# right_revision1_1.net
KiCad netlist of a schematic drawn in EAGLE
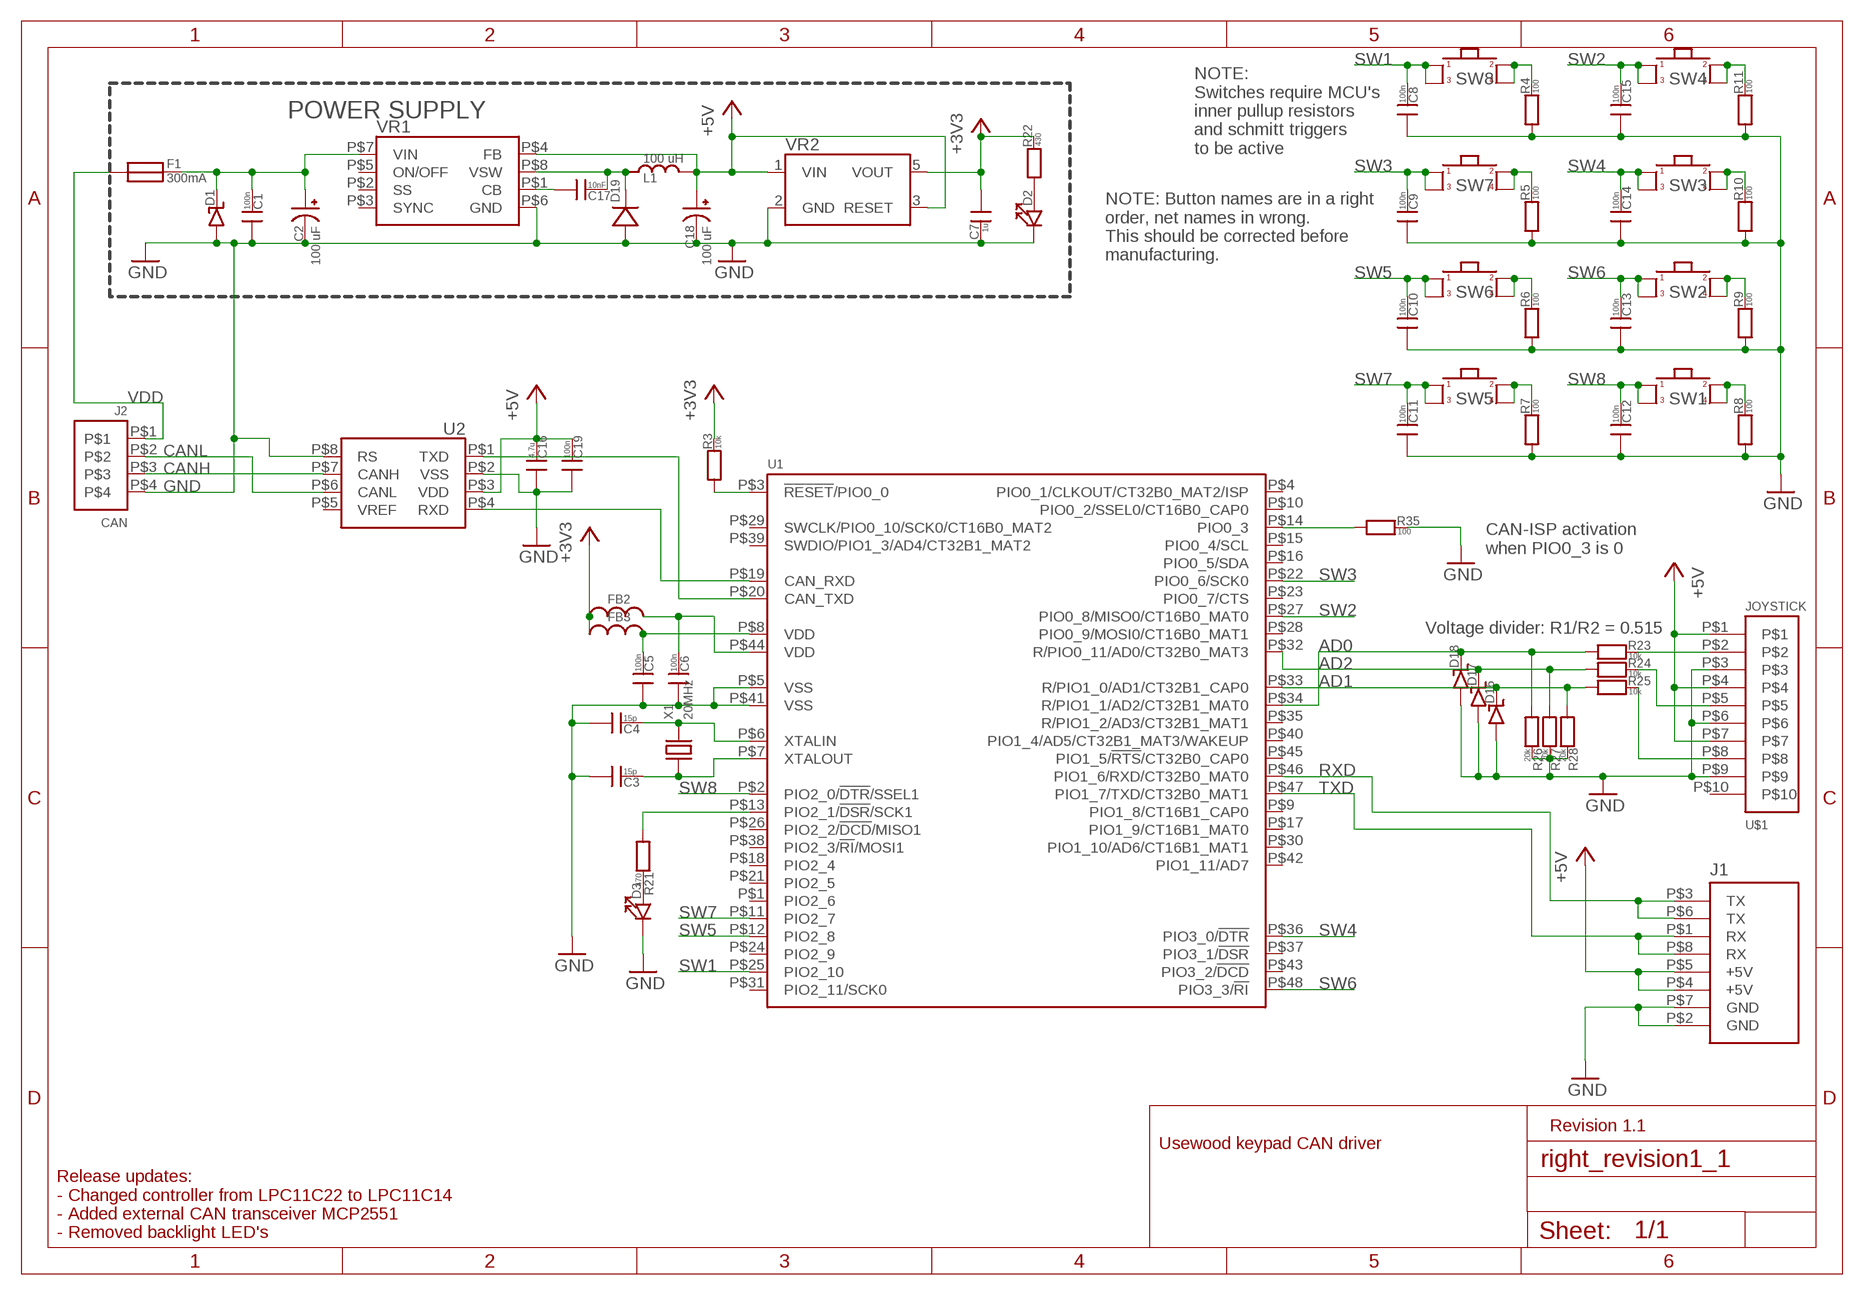
[diagram p0: schematic, sheet 1]

(export (version "E")
  (design (tool "Eeschema 10.0.6"))
  (components
    (comp (ref "C1")
      (value "100n")
      (footprint "eagle-import:0603_SILKSCREEN")
      (libsource (lib "eagle-import") (part "CAP0603_SILKSCREEN"))
    )
    (comp (ref "C2")
      (value "100 uF")
      (footprint "eagle-import:CAP_POL_SMD_10X10X10MM")
      (libsource (lib "eagle-import") (part "CAP_POLSMD_10X10X10MM"))
    )
    (comp (ref "C3")
      (value "15p")
      (footprint "eagle-import:0603_SILKSCREEN")
      (libsource (lib "eagle-import") (part "CAP0603_SILKSCREEN"))
    )
    (comp (ref "C4")
      (value "15p")
      (footprint "eagle-import:0603_SILKSCREEN")
      (libsource (lib "eagle-import") (part "CAP0603_SILKSCREEN"))
    )
    (comp (ref "C5")
      (value "100n")
      (footprint "eagle-import:0603_SILKSCREEN")
      (libsource (lib "eagle-import") (part "CAP0603_SILKSCREEN"))
    )
    (comp (ref "C6")
      (value "100n")
      (footprint "eagle-import:0603_SILKSCREEN")
      (libsource (lib "eagle-import") (part "CAP0603_SILKSCREEN"))
    )
    (comp (ref "C7")
      (value "1u")
      (footprint "eagle-import:0603_SILKSCREEN")
      (libsource (lib "eagle-import") (part "CAP0603_SILKSCREEN"))
    )
    (comp (ref "C8")
      (value "100n")
      (footprint "eagle-import:0603_SILKSCREEN")
      (libsource (lib "eagle-import") (part "CAP0603_SILKSCREEN"))
    )
    (comp (ref "C9")
      (value "100n")
      (footprint "eagle-import:0603_SILKSCREEN")
      (libsource (lib "eagle-import") (part "CAP0603_SILKSCREEN"))
    )
    (comp (ref "C10")
      (value "100n")
      (footprint "eagle-import:0603_SILKSCREEN")
      (libsource (lib "eagle-import") (part "CAP0603_SILKSCREEN"))
    )
    (comp (ref "C11")
      (value "100n")
      (footprint "eagle-import:0603_SILKSCREEN")
      (libsource (lib "eagle-import") (part "CAP0603_SILKSCREEN"))
    )
    (comp (ref "C12")
      (value "100n")
      (footprint "eagle-import:0603_SILKSCREEN")
      (libsource (lib "eagle-import") (part "CAP0603_SILKSCREEN"))
    )
    (comp (ref "C13")
      (value "100n")
      (footprint "eagle-import:0603_SILKSCREEN")
      (libsource (lib "eagle-import") (part "CAP0603_SILKSCREEN"))
    )
    (comp (ref "C14")
      (value "100n")
      (footprint "eagle-import:0603_SILKSCREEN")
      (libsource (lib "eagle-import") (part "CAP0603_SILKSCREEN"))
    )
    (comp (ref "C15")
      (value "100n")
      (footprint "eagle-import:0603_SILKSCREEN")
      (libsource (lib "eagle-import") (part "CAP0603_SILKSCREEN"))
    )
    (comp (ref "C16")
      (value "4.7u")
      (footprint "eagle-import:0603_SILKSCREEN")
      (libsource (lib "eagle-import") (part "CAP0603_SILKSCREEN"))
    )
    (comp (ref "C17")
      (value "10nF")
      (footprint "eagle-import:0603_SILKSCREEN")
      (libsource (lib "eagle-import") (part "CAP0603_SILKSCREEN"))
    )
    (comp (ref "C18")
      (value "100 uF")
      (footprint "eagle-import:CAP_POL_SMD_10X10X10MM")
      (libsource (lib "eagle-import") (part "CAP_POLSMD_10X10X10MM"))
    )
    (comp (ref "C19")
      (value "100n")
      (footprint "eagle-import:0603_SILKSCREEN")
      (libsource (lib "eagle-import") (part "CAP0603_SILKSCREEN"))
    )
    (comp (ref "D1")
      (value "DIODE_TVSDO-214AA")
      (footprint "eagle-import:DO-214AB")
      (libsource (lib "eagle-import") (part "DIODE_TVSDO-214AA"))
    )
    (comp (ref "D2")
      (value "LED0603_SILKSCREEN")
      (footprint "eagle-import:0603_SILKSCREEN")
      (libsource (lib "eagle-import") (part "LED0603_SILKSCREEN"))
    )
    (comp (ref "D3")
      (value "LED0603_SILKSCREEN")
      (footprint "eagle-import:0603_SILKSCREEN")
      (libsource (lib "eagle-import") (part "LED0603_SILKSCREEN"))
    )
    (comp (ref "D16")
      (value "DIODE_ZENERSDO123")
      (footprint "eagle-import:SOD123")
      (libsource (lib "eagle-import") (part "DIODE_ZENERSDO123"))
    )
    (comp (ref "D17")
      (value "DIODE_ZENERSDO123")
      (footprint "eagle-import:SOD123")
      (libsource (lib "eagle-import") (part "DIODE_ZENERSDO123"))
    )
    (comp (ref "D18")
      (value "DIODE_ZENERSDO123")
      (footprint "eagle-import:SOD123")
      (libsource (lib "eagle-import") (part "DIODE_ZENERSDO123"))
    )
    (comp (ref "D19")
      (value "DIODEDO219AB")
      (footprint "eagle-import:DO219AB")
      (libsource (lib "eagle-import") (part "DIODEDO219AB"))
    )
    (comp (ref "F1")
      (value "300mA")
      (footprint "eagle-import:FUSE_100MA")
      (libsource (lib "eagle-import") (part "FUSE100MA"))
    )
    (comp (ref "FB2")
      (value "FERRITE0603_SILKSCREEN")
      (footprint "eagle-import:0603_SILKSCREEN")
      (libsource (lib "eagle-import") (part "FERRITE0603_SILKSCREEN"))
    )
    (comp (ref "FB3")
      (value "FERRITE0603_SILKSCREEN")
      (footprint "eagle-import:0603_SILKSCREEN")
      (libsource (lib "eagle-import") (part "FERRITE0603_SILKSCREEN"))
    )
    (comp (ref "J1")
      (value "HEADER_USART_2_TH")
      (footprint "eagle-import:HEADER_USART_2_TH")
      (libsource (lib "eagle-import") (part "HEADER_USART_2_TH"))
    )
    (comp (ref "J2")
      (value "CAN")
      (footprint "eagle-import:MOLEX_MICRO-FIT_4WAY")
      (libsource (lib "eagle-import") (part "MOLEX_MICRO-FIT_4WAYTH"))
    )
    (comp (ref "L1")
      (value "100 uH")
      (footprint "eagle-import:INDUCTOR_BOURNS_10X13X5MM")
      (libsource (lib "eagle-import") (part "INDUCTORBOURNS_10X13X5MM"))
    )
    (comp (ref "R3")
      (value "10k")
      (footprint "eagle-import:0603_SILKSCREEN")
      (libsource (lib "eagle-import") (part "RES0604_SILKSCREEN"))
    )
    (comp (ref "R4")
      (value "100")
      (footprint "eagle-import:0603_SILKSCREEN")
      (libsource (lib "eagle-import") (part "RES0604_SILKSCREEN"))
    )
    (comp (ref "R5")
      (value "100")
      (footprint "eagle-import:0603_SILKSCREEN")
      (libsource (lib "eagle-import") (part "RES0604_SILKSCREEN"))
    )
    (comp (ref "R6")
      (value "100")
      (footprint "eagle-import:0603_SILKSCREEN")
      (libsource (lib "eagle-import") (part "RES0604_SILKSCREEN"))
    )
    (comp (ref "R7")
      (value "100")
      (footprint "eagle-import:0603_SILKSCREEN")
      (libsource (lib "eagle-import") (part "RES0604_SILKSCREEN"))
    )
    (comp (ref "R8")
      (value "100")
      (footprint "eagle-import:0603_SILKSCREEN")
      (libsource (lib "eagle-import") (part "RES0604_SILKSCREEN"))
    )
    (comp (ref "R9")
      (value "100")
      (footprint "eagle-import:0603_SILKSCREEN")
      (libsource (lib "eagle-import") (part "RES0604_SILKSCREEN"))
    )
    (comp (ref "R10")
      (value "100")
      (footprint "eagle-import:0603_SILKSCREEN")
      (libsource (lib "eagle-import") (part "RES0604_SILKSCREEN"))
    )
    (comp (ref "R11")
      (value "100")
      (footprint "eagle-import:0603_SILKSCREEN")
      (libsource (lib "eagle-import") (part "RES0604_SILKSCREEN"))
    )
    (comp (ref "R21")
      (value "470")
      (footprint "eagle-import:0603_SILKSCREEN")
      (libsource (lib "eagle-import") (part "RES0604_SILKSCREEN"))
    )
    (comp (ref "R22")
      (value "430")
      (footprint "eagle-import:0603_SILKSCREEN")
      (libsource (lib "eagle-import") (part "RES0604_SILKSCREEN"))
    )
    (comp (ref "R23")
      (value "10k")
      (footprint "eagle-import:0603_SILKSCREEN")
      (libsource (lib "eagle-import") (part "RES0604_SILKSCREEN"))
    )
    (comp (ref "R24")
      (value "10k")
      (footprint "eagle-import:0603_SILKSCREEN")
      (libsource (lib "eagle-import") (part "RES0604_SILKSCREEN"))
    )
    (comp (ref "R25")
      (value "10k")
      (footprint "eagle-import:0603_SILKSCREEN")
      (libsource (lib "eagle-import") (part "RES0604_SILKSCREEN"))
    )
    (comp (ref "R26")
      (value "20k")
      (footprint "eagle-import:0603_SILKSCREEN")
      (libsource (lib "eagle-import") (part "RES0604_SILKSCREEN"))
    )
    (comp (ref "R27")
      (value "20k")
      (footprint "eagle-import:0603_SILKSCREEN")
      (libsource (lib "eagle-import") (part "RES0604_SILKSCREEN"))
    )
    (comp (ref "R28")
      (value "20k")
      (footprint "eagle-import:0603_SILKSCREEN")
      (libsource (lib "eagle-import") (part "RES0604_SILKSCREEN"))
    )
    (comp (ref "R35")
      (value "100")
      (footprint "eagle-import:0603_SILKSCREEN")
      (libsource (lib "eagle-import") (part "RES0604_SILKSCREEN"))
    )
    (comp (ref "SW1")
      (value "SWITCH12X12MM_CENTER_HOLE")
      (footprint "eagle-import:SWITCH_12X12MM_CENTER_HOLE")
      (libsource (lib "eagle-import") (part "SWITCH12X12MM_CENTER_HOLE"))
    )
    (comp (ref "SW2")
      (value "SWITCH12X12MM_CENTER_HOLE")
      (footprint "eagle-import:SWITCH_12X12MM_CENTER_HOLE")
      (libsource (lib "eagle-import") (part "SWITCH12X12MM_CENTER_HOLE"))
    )
    (comp (ref "SW3")
      (value "SWITCH12X12MM_CENTER_HOLE")
      (footprint "eagle-import:SWITCH_12X12MM_CENTER_HOLE")
      (libsource (lib "eagle-import") (part "SWITCH12X12MM_CENTER_HOLE"))
    )
    (comp (ref "SW4")
      (value "SWITCH12X12MM_CENTER_HOLE")
      (footprint "eagle-import:SWITCH_12X12MM_CENTER_HOLE")
      (libsource (lib "eagle-import") (part "SWITCH12X12MM_CENTER_HOLE"))
    )
    (comp (ref "SW5")
      (value "SWITCH12X12MM_CENTER_HOLE")
      (footprint "eagle-import:SWITCH_12X12MM_CENTER_HOLE")
      (libsource (lib "eagle-import") (part "SWITCH12X12MM_CENTER_HOLE"))
    )
    (comp (ref "SW6")
      (value "SWITCH12X12MM_CENTER_HOLE")
      (footprint "eagle-import:SWITCH_12X12MM_CENTER_HOLE")
      (libsource (lib "eagle-import") (part "SWITCH12X12MM_CENTER_HOLE"))
    )
    (comp (ref "SW7")
      (value "SWITCH12X12MM_CENTER_HOLE")
      (footprint "eagle-import:SWITCH_12X12MM_CENTER_HOLE")
      (libsource (lib "eagle-import") (part "SWITCH12X12MM_CENTER_HOLE"))
    )
    (comp (ref "SW8")
      (value "SWITCH12X12MM_CENTER_HOLE")
      (footprint "eagle-import:SWITCH_12X12MM_CENTER_HOLE")
      (libsource (lib "eagle-import") (part "SWITCH12X12MM_CENTER_HOLE"))
    )
    (comp (ref "U$1")
      (value "JOYSTICK")
      (footprint "eagle-import:MOLEX-MICRO-FIT_10WAY")
      (libsource (lib "eagle-import") (part "MOLEX_MICRO-FIT_10WAYTH"))
    )
    (comp (ref "U1")
      (value "LPC11C14_QFP48")
      (footprint "eagle-import:QFP48")
      (libsource (lib "eagle-import") (part "LPC11C14_QFP48"))
    )
    (comp (ref "U2")
      (value "MCP2551_SOIC8")
      (footprint "eagle-import:SOIC8")
      (libsource (lib "eagle-import") (part "MCP2551_SOIC8"))
    )
    (comp (ref "VR1")
      (value "LM2671SOIC8")
      (footprint "eagle-import:SOIC8")
      (libsource (lib "eagle-import") (part "LM2671SOIC8"))
    )
    (comp (ref "VR2")
      (value "LP2985SOP5")
      (footprint "eagle-import:SOP5")
      (libsource (lib "eagle-import") (part "LP2985SOP5"))
    )
    (comp (ref "X1")
      (value "20MHz")
      (footprint "eagle-import:XTAL_SMD_5X3.2")
      (libsource (lib "eagle-import") (part "XTALSMD_5X3.2"))
    )
  )
  (nets
    (net (code "1") (name "+3V3") (class "Default")
      (node (ref "C7") (pin "0") (pinfunction "P$1_0") (pintype "bidirectional"))
      (node (ref "FB2") (pin "0") (pinfunction "P$1_0") (pintype "bidirectional"))
      (node (ref "FB3") (pin "0") (pinfunction "P$1_0") (pintype "bidirectional"))
      (node (ref "R22") (pin "1") (pinfunction "P$2_1") (pintype "bidirectional"))
      (node (ref "R3") (pin "1") (pinfunction "P$2_1") (pintype "bidirectional"))
      (node (ref "VR2") (pin "5") (pinfunction "VOUT_5") (pintype "bidirectional"))
    )
    (net (code "2") (name "+5V") (class "Default")
      (node (ref "C16") (pin "1") (pinfunction "P$2_1") (pintype "bidirectional"))
      (node (ref "C18") (pin "+") (pinfunction "+_+") (pintype "bidirectional"))
      (node (ref "C19") (pin "1") (pinfunction "P$2_1") (pintype "bidirectional"))
      (node (ref "J1") (pin "P$4") (pinfunction "+5V_P$4") (pintype "bidirectional"))
      (node (ref "J1") (pin "P$5") (pinfunction "+5V_P$5") (pintype "bidirectional"))
      (node (ref "L1") (pin "P$2") (pinfunction "P$2_P$2") (pintype "bidirectional"))
      (node (ref "U$1") (pin "P$1") (pinfunction "P$1_P$1") (pintype "bidirectional"))
      (node (ref "U$1") (pin "P$4") (pinfunction "P$4_P$4") (pintype "bidirectional"))
      (node (ref "U$1") (pin "P$7") (pinfunction "P$7_P$7") (pintype "bidirectional"))
      (node (ref "U2") (pin "P$3") (pinfunction "VDD_P$3") (pintype "bidirectional"))
      (node (ref "VR1") (pin "P$4") (pinfunction "FB_P$4") (pintype "bidirectional"))
      (node (ref "VR2") (pin "1") (pinfunction "VIN_1") (pintype "bidirectional"))
      (node (ref "VR2") (pin "3") (pinfunction "RESET_3") (pintype "bidirectional"))
    )
    (net (code "3") (name "/AD0") (class "Default")
      (node (ref "D18") (pin "P$2") (pinfunction "N_P$2") (pintype "bidirectional"))
      (node (ref "R23") (pin "0") (pinfunction "P$1_0") (pintype "bidirectional"))
      (node (ref "R26") (pin "0") (pinfunction "P$1_0") (pintype "bidirectional"))
      (node (ref "U1") (pin "P$34") (pinfunction "R/PIO1_1/AD2/CT32B1_MAT0_P$34") (pintype "bidirectional"))
    )
    (net (code "4") (name "/AD1") (class "Default")
      (node (ref "D16") (pin "P$2") (pinfunction "N_P$2") (pintype "bidirectional"))
      (node (ref "R25") (pin "0") (pinfunction "P$1_0") (pintype "bidirectional"))
      (node (ref "R28") (pin "0") (pinfunction "P$1_0") (pintype "bidirectional"))
      (node (ref "U1") (pin "P$33") (pinfunction "R/PIO1_0/AD1/CT32B1_CAP0_P$33") (pintype "bidirectional"))
    )
    (net (code "5") (name "/AD2") (class "Default")
      (node (ref "D17") (pin "P$2") (pinfunction "N_P$2") (pintype "bidirectional"))
      (node (ref "R24") (pin "0") (pinfunction "P$1_0") (pintype "bidirectional"))
      (node (ref "R27") (pin "0") (pinfunction "P$1_0") (pintype "bidirectional"))
      (node (ref "U1") (pin "P$32") (pinfunction "R/PIO0_11/AD0/CT32B0_MAT3_P$32") (pintype "bidirectional"))
    )
    (net (code "6") (name "/CANH") (class "Default")
      (node (ref "J2") (pin "P$3") (pinfunction "P$3_P$3") (pintype "bidirectional"))
      (node (ref "U2") (pin "P$7") (pinfunction "CANH_P$7") (pintype "bidirectional"))
    )
    (net (code "7") (name "/CANL") (class "Default")
      (node (ref "J2") (pin "P$2") (pinfunction "P$2_P$2") (pintype "bidirectional"))
      (node (ref "U2") (pin "P$6") (pinfunction "CANL_P$6") (pintype "bidirectional"))
    )
    (net (code "8") (name "/RXD") (class "Default")
      (node (ref "J1") (pin "P$3") (pinfunction "TX_P$3") (pintype "bidirectional"))
      (node (ref "J1") (pin "P$6") (pinfunction "TX_P$6") (pintype "bidirectional"))
      (node (ref "U1") (pin "P$46") (pinfunction "PIO1_6/RXD/CT32B0_MAT0_P$46") (pintype "bidirectional"))
    )
    (net (code "9") (name "/SW1") (class "Default")
      (node (ref "C8") (pin "1") (pinfunction "P$2_1") (pintype "bidirectional"))
      (node (ref "SW8") (pin "P$1") (pinfunction "P$1_P$1") (pintype "bidirectional"))
      (node (ref "SW8") (pin "P$2") (pinfunction "P$3_P$2") (pintype "bidirectional"))
      (node (ref "U1") (pin "P$25") (pinfunction "PIO2_10_P$25") (pintype "bidirectional"))
    )
    (net (code "10") (name "/SW2") (class "Default")
      (node (ref "C15") (pin "1") (pinfunction "P$2_1") (pintype "bidirectional"))
      (node (ref "SW4") (pin "P$1") (pinfunction "P$1_P$1") (pintype "bidirectional"))
      (node (ref "SW4") (pin "P$2") (pinfunction "P$3_P$2") (pintype "bidirectional"))
      (node (ref "U1") (pin "P$27") (pinfunction "PIO0_8/MISO0/CT16B0_MAT0_P$27") (pintype "bidirectional"))
    )
    (net (code "11") (name "/SW3") (class "Default")
      (node (ref "C9") (pin "1") (pinfunction "P$2_1") (pintype "bidirectional"))
      (node (ref "SW7") (pin "P$1") (pinfunction "P$1_P$1") (pintype "bidirectional"))
      (node (ref "SW7") (pin "P$2") (pinfunction "P$3_P$2") (pintype "bidirectional"))
      (node (ref "U1") (pin "P$22") (pinfunction "PIO0_6/SCK0_P$22") (pintype "bidirectional"))
    )
    (net (code "12") (name "/SW4") (class "Default")
      (node (ref "C14") (pin "1") (pinfunction "P$2_1") (pintype "bidirectional"))
      (node (ref "SW3") (pin "P$1") (pinfunction "P$1_P$1") (pintype "bidirectional"))
      (node (ref "SW3") (pin "P$2") (pinfunction "P$3_P$2") (pintype "bidirectional"))
      (node (ref "U1") (pin "P$36") (pinfunction "PIO3_0/~{DTR}_P$36") (pintype "bidirectional"))
    )
    (net (code "13") (name "/SW5") (class "Default")
      (node (ref "C10") (pin "1") (pinfunction "P$2_1") (pintype "bidirectional"))
      (node (ref "SW6") (pin "P$1") (pinfunction "P$1_P$1") (pintype "bidirectional"))
      (node (ref "SW6") (pin "P$2") (pinfunction "P$3_P$2") (pintype "bidirectional"))
      (node (ref "U1") (pin "P$12") (pinfunction "PIO2_8_P$12") (pintype "bidirectional"))
    )
    (net (code "14") (name "/SW6") (class "Default")
      (node (ref "C13") (pin "1") (pinfunction "P$2_1") (pintype "bidirectional"))
      (node (ref "SW2") (pin "P$1") (pinfunction "P$1_P$1") (pintype "bidirectional"))
      (node (ref "SW2") (pin "P$2") (pinfunction "P$3_P$2") (pintype "bidirectional"))
      (node (ref "U1") (pin "P$48") (pinfunction "PIO3_3/~{RI}_P$48") (pintype "bidirectional"))
    )
    (net (code "15") (name "/SW7") (class "Default")
      (node (ref "C11") (pin "1") (pinfunction "P$2_1") (pintype "bidirectional"))
      (node (ref "SW5") (pin "P$1") (pinfunction "P$1_P$1") (pintype "bidirectional"))
      (node (ref "SW5") (pin "P$2") (pinfunction "P$3_P$2") (pintype "bidirectional"))
      (node (ref "U1") (pin "P$11") (pinfunction "PIO2_7_P$11") (pintype "bidirectional"))
    )
    (net (code "16") (name "/SW8") (class "Default")
      (node (ref "C12") (pin "1") (pinfunction "P$2_1") (pintype "bidirectional"))
      (node (ref "SW1") (pin "P$1") (pinfunction "P$1_P$1") (pintype "bidirectional"))
      (node (ref "SW1") (pin "P$2") (pinfunction "P$3_P$2") (pintype "bidirectional"))
      (node (ref "U1") (pin "P$2") (pinfunction "PIO2_0/~{DTR}/SSEL1_P$2") (pintype "bidirectional"))
    )
    (net (code "17") (name "/TXD") (class "Default")
      (node (ref "J1") (pin "P$1") (pinfunction "RX_P$1") (pintype "bidirectional"))
      (node (ref "J1") (pin "P$8") (pinfunction "RX_P$8") (pintype "bidirectional"))
      (node (ref "U1") (pin "P$47") (pinfunction "PIO1_7/TXD/CT32B0_MAT1_P$47") (pintype "bidirectional"))
    )
    (net (code "18") (name "/VDD") (class "Default")
      (node (ref "F1") (pin "P$1") (pinfunction "P$1_P$1") (pintype "bidirectional"))
      (node (ref "J2") (pin "P$1") (pinfunction "P$1_P$1") (pintype "bidirectional"))
    )
    (net (code "19") (name "GND") (class "Default")
      (node (ref "C1") (pin "0") (pinfunction "P$1_0") (pintype "bidirectional"))
      (node (ref "C10") (pin "0") (pinfunction "P$1_0") (pintype "bidirectional"))
      (node (ref "C11") (pin "0") (pinfunction "P$1_0") (pintype "bidirectional"))
      (node (ref "C12") (pin "0") (pinfunction "P$1_0") (pintype "bidirectional"))
      (node (ref "C13") (pin "0") (pinfunction "P$1_0") (pintype "bidirectional"))
      (node (ref "C14") (pin "0") (pinfunction "P$1_0") (pintype "bidirectional"))
      (node (ref "C15") (pin "0") (pinfunction "P$1_0") (pintype "bidirectional"))
      (node (ref "C16") (pin "0") (pinfunction "P$1_0") (pintype "bidirectional"))
      (node (ref "C18") (pin "-") (pinfunction "-_-") (pintype "bidirectional"))
      (node (ref "C19") (pin "0") (pinfunction "P$1_0") (pintype "bidirectional"))
      (node (ref "C2") (pin "-") (pinfunction "-_-") (pintype "bidirectional"))
      (node (ref "C3") (pin "0") (pinfunction "P$1_0") (pintype "bidirectional"))
      (node (ref "C4") (pin "0") (pinfunction "P$1_0") (pintype "bidirectional"))
      (node (ref "C5") (pin "0") (pinfunction "P$1_0") (pintype "bidirectional"))
      (node (ref "C6") (pin "0") (pinfunction "P$1_0") (pintype "bidirectional"))
      (node (ref "C7") (pin "1") (pinfunction "P$2_1") (pintype "bidirectional"))
      (node (ref "C8") (pin "0") (pinfunction "P$1_0") (pintype "bidirectional"))
      (node (ref "C9") (pin "0") (pinfunction "P$1_0") (pintype "bidirectional"))
      (node (ref "D1") (pin "P$1") (pinfunction "P_P$1") (pintype "bidirectional"))
      (node (ref "D16") (pin "P$1") (pinfunction "P_P$1") (pintype "bidirectional"))
      (node (ref "D17") (pin "P$1") (pinfunction "P_P$1") (pintype "bidirectional"))
      (node (ref "D18") (pin "P$1") (pinfunction "P_P$1") (pintype "bidirectional"))
      (node (ref "D19") (pin "P$1") (pinfunction "P_P$1") (pintype "bidirectional"))
      (node (ref "D2") (pin "1") (pinfunction "1_1") (pintype "bidirectional"))
      (node (ref "D3") (pin "1") (pinfunction "1_1") (pintype "bidirectional"))
      (node (ref "J1") (pin "P$2") (pinfunction "GND_P$2") (pintype "bidirectional"))
      (node (ref "J1") (pin "P$7") (pinfunction "GND_P$7") (pintype "bidirectional"))
      (node (ref "J2") (pin "P$4") (pinfunction "P$4_P$4") (pintype "bidirectional"))
      (node (ref "R10") (pin "0") (pinfunction "P$1_0") (pintype "bidirectional"))
      (node (ref "R11") (pin "0") (pinfunction "P$1_0") (pintype "bidirectional"))
      (node (ref "R26") (pin "1") (pinfunction "P$2_1") (pintype "bidirectional"))
      (node (ref "R27") (pin "1") (pinfunction "P$2_1") (pintype "bidirectional"))
      (node (ref "R28") (pin "1") (pinfunction "P$2_1") (pintype "bidirectional"))
      (node (ref "R35") (pin "1") (pinfunction "P$2_1") (pintype "bidirectional"))
      (node (ref "R4") (pin "0") (pinfunction "P$1_0") (pintype "bidirectional"))
      (node (ref "R5") (pin "0") (pinfunction "P$1_0") (pintype "bidirectional"))
      (node (ref "R6") (pin "0") (pinfunction "P$1_0") (pintype "bidirectional"))
      (node (ref "R7") (pin "0") (pinfunction "P$1_0") (pintype "bidirectional"))
      (node (ref "R8") (pin "0") (pinfunction "P$1_0") (pintype "bidirectional"))
      (node (ref "R9") (pin "0") (pinfunction "P$1_0") (pintype "bidirectional"))
      (node (ref "U$1") (pin "P$3") (pinfunction "P$3_P$3") (pintype "bidirectional"))
      (node (ref "U$1") (pin "P$6") (pinfunction "P$6_P$6") (pintype "bidirectional"))
      (node (ref "U$1") (pin "P$9") (pinfunction "P$9_P$9") (pintype "bidirectional"))
      (node (ref "U1") (pin "P$41") (pinfunction "VSS_P$41") (pintype "bidirectional"))
      (node (ref "U1") (pin "P$5") (pinfunction "VSS_P$5") (pintype "bidirectional"))
      (node (ref "U2") (pin "P$2") (pinfunction "VSS_P$2") (pintype "bidirectional"))
      (node (ref "U2") (pin "P$8") (pinfunction "RS_P$8") (pintype "bidirectional"))
      (node (ref "VR1") (pin "P$6") (pinfunction "GND_P$6") (pintype "bidirectional"))
      (node (ref "VR2") (pin "2") (pinfunction "GND_2") (pintype "bidirectional"))
    )
    (net (code "20") (name "Net-(C1-P$2)") (class "Default")
      (node (ref "C1") (pin "1") (pinfunction "P$2_1") (pintype "bidirectional"))
      (node (ref "C2") (pin "+") (pinfunction "+_+") (pintype "bidirectional"))
      (node (ref "D1") (pin "P$2") (pinfunction "N_P$2") (pintype "bidirectional"))
      (node (ref "F1") (pin "P$2") (pinfunction "P$2_P$2") (pintype "bidirectional"))
      (node (ref "VR1") (pin "P$7") (pinfunction "VIN_P$7") (pintype "bidirectional"))
    )
    (net (code "21") (name "Net-(C3-P$2)") (class "Default")
      (node (ref "C3") (pin "1") (pinfunction "P$2_1") (pintype "bidirectional"))
      (node (ref "U1") (pin "P$7") (pinfunction "XTALOUT_P$7") (pintype "bidirectional"))
      (node (ref "X1") (pin "P$1") (pinfunction "P$1_P$1") (pintype "bidirectional"))
    )
    (net (code "22") (name "Net-(C4-P$2)") (class "Default")
      (node (ref "C4") (pin "1") (pinfunction "P$2_1") (pintype "bidirectional"))
      (node (ref "U1") (pin "P$6") (pinfunction "XTALIN_P$6") (pintype "bidirectional"))
      (node (ref "X1") (pin "P$2") (pinfunction "P$2_P$2") (pintype "bidirectional"))
    )
    (net (code "23") (name "Net-(C5-P$2)") (class "Default")
      (node (ref "C5") (pin "1") (pinfunction "P$2_1") (pintype "bidirectional"))
      (node (ref "FB3") (pin "1") (pinfunction "P$2_1") (pintype "bidirectional"))
      (node (ref "U1") (pin "P$8") (pinfunction "VDD_P$8") (pintype "bidirectional"))
    )
    (net (code "24") (name "Net-(C6-P$2)") (class "Default")
      (node (ref "C6") (pin "1") (pinfunction "P$2_1") (pintype "bidirectional"))
      (node (ref "FB2") (pin "1") (pinfunction "P$2_1") (pintype "bidirectional"))
      (node (ref "U1") (pin "P$44") (pinfunction "VDD_P$44") (pintype "bidirectional"))
    )
    (net (code "25") (name "Net-(C17-P$1)") (class "Default")
      (node (ref "C17") (pin "0") (pinfunction "P$1_0") (pintype "bidirectional"))
      (node (ref "VR1") (pin "P$1") (pinfunction "CB_P$1") (pintype "bidirectional"))
    )
    (net (code "26") (name "Net-(C17-P$2)") (class "Default")
      (node (ref "C17") (pin "1") (pinfunction "P$2_1") (pintype "bidirectional"))
      (node (ref "D19") (pin "P$2") (pinfunction "N_P$2") (pintype "bidirectional"))
      (node (ref "L1") (pin "P$1") (pinfunction "P$1_P$1") (pintype "bidirectional"))
      (node (ref "VR1") (pin "P$8") (pinfunction "VSW_P$8") (pintype "bidirectional"))
    )
    (net (code "27") (name "Net-(R3-P$1)") (class "Default")
      (node (ref "R3") (pin "0") (pinfunction "P$1_0") (pintype "bidirectional"))
      (node (ref "U1") (pin "P$3") (pinfunction "~{RESET}/PIO0_0_P$3") (pintype "bidirectional"))
    )
    (net (code "28") (name "Net-(R4-P$2)") (class "Default")
      (node (ref "R4") (pin "1") (pinfunction "P$2_1") (pintype "bidirectional"))
      (node (ref "SW8") (pin "P$3") (pinfunction "P$2_P$3") (pintype "bidirectional"))
      (node (ref "SW8") (pin "P$4") (pinfunction "P$4_P$4") (pintype "bidirectional"))
    )
    (net (code "29") (name "Net-(R5-P$2)") (class "Default")
      (node (ref "R5") (pin "1") (pinfunction "P$2_1") (pintype "bidirectional"))
      (node (ref "SW7") (pin "P$3") (pinfunction "P$2_P$3") (pintype "bidirectional"))
      (node (ref "SW7") (pin "P$4") (pinfunction "P$4_P$4") (pintype "bidirectional"))
    )
    (net (code "30") (name "Net-(R6-P$2)") (class "Default")
      (node (ref "R6") (pin "1") (pinfunction "P$2_1") (pintype "bidirectional"))
      (node (ref "SW6") (pin "P$3") (pinfunction "P$2_P$3") (pintype "bidirectional"))
      (node (ref "SW6") (pin "P$4") (pinfunction "P$4_P$4") (pintype "bidirectional"))
    )
    (net (code "31") (name "Net-(R7-P$2)") (class "Default")
      (node (ref "R7") (pin "1") (pinfunction "P$2_1") (pintype "bidirectional"))
      (node (ref "SW5") (pin "P$3") (pinfunction "P$2_P$3") (pintype "bidirectional"))
      (node (ref "SW5") (pin "P$4") (pinfunction "P$4_P$4") (pintype "bidirectional"))
    )
    (net (code "32") (name "Net-(R8-P$2)") (class "Default")
      (node (ref "R8") (pin "1") (pinfunction "P$2_1") (pintype "bidirectional"))
      (node (ref "SW1") (pin "P$3") (pinfunction "P$2_P$3") (pintype "bidirectional"))
      (node (ref "SW1") (pin "P$4") (pinfunction "P$4_P$4") (pintype "bidirectional"))
    )
    (net (code "33") (name "Net-(R9-P$2)") (class "Default")
      (node (ref "R9") (pin "1") (pinfunction "P$2_1") (pintype "bidirectional"))
      (node (ref "SW2") (pin "P$3") (pinfunction "P$2_P$3") (pintype "bidirectional"))
      (node (ref "SW2") (pin "P$4") (pinfunction "P$4_P$4") (pintype "bidirectional"))
    )
    (net (code "34") (name "Net-(R10-P$2)") (class "Default")
      (node (ref "R10") (pin "1") (pinfunction "P$2_1") (pintype "bidirectional"))
      (node (ref "SW3") (pin "P$3") (pinfunction "P$2_P$3") (pintype "bidirectional"))
      (node (ref "SW3") (pin "P$4") (pinfunction "P$4_P$4") (pintype "bidirectional"))
    )
    (net (code "35") (name "Net-(R11-P$2)") (class "Default")
      (node (ref "R11") (pin "1") (pinfunction "P$2_1") (pintype "bidirectional"))
      (node (ref "SW4") (pin "P$3") (pinfunction "P$2_P$3") (pintype "bidirectional"))
      (node (ref "SW4") (pin "P$4") (pinfunction "P$4_P$4") (pintype "bidirectional"))
    )
    (net (code "36") (name "Net-(R21-P$1)") (class "Default")
      (node (ref "R21") (pin "0") (pinfunction "P$1_0") (pintype "bidirectional"))
      (node (ref "U1") (pin "P$13") (pinfunction "PIO2_1/~{DSR}/SCK1_P$13") (pintype "bidirectional"))
    )
    (net (code "37") (name "Net-(R21-P$2)") (class "Default")
      (node (ref "D3") (pin "0") (pinfunction "0_0") (pintype "bidirectional"))
      (node (ref "R21") (pin "1") (pinfunction "P$2_1") (pintype "bidirectional"))
    )
    (net (code "38") (name "Net-(R22-P$1)") (class "Default")
      (node (ref "D2") (pin "0") (pinfunction "0_0") (pintype "bidirectional"))
      (node (ref "R22") (pin "0") (pinfunction "P$1_0") (pintype "bidirectional"))
    )
    (net (code "39") (name "Net-(R23-P$2)") (class "Default")
      (node (ref "R23") (pin "1") (pinfunction "P$2_1") (pintype "bidirectional"))
      (node (ref "U$1") (pin "P$2") (pinfunction "P$2_P$2") (pintype "bidirectional"))
    )
    (net (code "40") (name "Net-(R24-P$2)") (class "Default")
      (node (ref "R24") (pin "1") (pinfunction "P$2_1") (pintype "bidirectional"))
      (node (ref "U$1") (pin "P$5") (pinfunction "P$5_P$5") (pintype "bidirectional"))
    )
    (net (code "41") (name "Net-(R25-P$2)") (class "Default")
      (node (ref "R25") (pin "1") (pinfunction "P$2_1") (pintype "bidirectional"))
      (node (ref "U$1") (pin "P$8") (pinfunction "P$8_P$8") (pintype "bidirectional"))
    )
    (net (code "42") (name "Net-(R35-P$1)") (class "Default")
      (node (ref "R35") (pin "0") (pinfunction "P$1_0") (pintype "bidirectional"))
      (node (ref "U1") (pin "P$14") (pinfunction "PIO0_3_P$14") (pintype "bidirectional"))
    )
    (net (code "43") (name "Net-(U1-CAN_RXD)") (class "Default")
      (node (ref "U1") (pin "P$19") (pinfunction "CAN_RXD_P$19") (pintype "bidirectional"))
      (node (ref "U2") (pin "P$4") (pinfunction "RXD_P$4") (pintype "bidirectional"))
    )
    (net (code "44") (name "Net-(U1-CAN_TXD)") (class "Default")
      (node (ref "U1") (pin "P$20") (pinfunction "CAN_TXD_P$20") (pintype "bidirectional"))
      (node (ref "U2") (pin "P$1") (pinfunction "TXD_P$1") (pintype "bidirectional"))
    )
    (net (code "45") (name "unconnected-(U$1-PadP$10)") (class "Default")
      (node (ref "U$1") (pin "P$10") (pinfunction "P$10_P$10") (pintype "bidirectional"))
    )
    (net (code "46") (name "unconnected-(U1-PIO0_1{slash}CLKOUT{slash}CT32B0_MAT2{slash}ISP-PadP$4)") (class "Default")
      (node (ref "U1") (pin "P$4") (pinfunction "PIO0_1/CLKOUT/CT32B0_MAT2/ISP_P$4") (pintype "bidirectional"))
    )
    (net (code "47") (name "unconnected-(U1-PIO0_2{slash}SSEL0{slash}CT16B0_CAP0-PadP$10)") (class "Default")
      (node (ref "U1") (pin "P$10") (pinfunction "PIO0_2/SSEL0/CT16B0_CAP0_P$10") (pintype "bidirectional"))
    )
    (net (code "48") (name "unconnected-(U1-PIO0_4{slash}SCL-PadP$15)") (class "Default")
      (node (ref "U1") (pin "P$15") (pinfunction "PIO0_4/SCL_P$15") (pintype "bidirectional"))
    )
    (net (code "49") (name "unconnected-(U1-PIO0_5{slash}SDA-PadP$16)") (class "Default")
      (node (ref "U1") (pin "P$16") (pinfunction "PIO0_5/SDA_P$16") (pintype "bidirectional"))
    )
    (net (code "50") (name "unconnected-(U1-PIO0_7{slash}CTS-PadP$23)") (class "Default")
      (node (ref "U1") (pin "P$23") (pinfunction "PIO0_7/CTS_P$23") (pintype "bidirectional"))
    )
    (net (code "51") (name "unconnected-(U1-PIO0_9{slash}MOSI0{slash}CT16B0_MAT1-PadP$28)") (class "Default")
      (node (ref "U1") (pin "P$28") (pinfunction "PIO0_9/MOSI0/CT16B0_MAT1_P$28") (pintype "bidirectional"))
    )
    (net (code "52") (name "unconnected-(U1-PIO1_4{slash}AD5{slash}CT32B1_MAT3{slash}WAKEUP-PadP$40)") (class "Default")
      (node (ref "U1") (pin "P$40") (pinfunction "PIO1_4/AD5/CT32B1_MAT3/WAKEUP_P$40") (pintype "bidirectional"))
    )
    (net (code "53") (name "unconnected-(U1-PIO1_5{slash}~{RTS}{slash}CT32B0_CAP0-PadP$45)") (class "Default")
      (node (ref "U1") (pin "P$45") (pinfunction "PIO1_5/~{RTS}/CT32B0_CAP0_P$45") (pintype "bidirectional"))
    )
    (net (code "54") (name "unconnected-(U1-PIO1_8{slash}CT16B1_CAP0-PadP$9)") (class "Default")
      (node (ref "U1") (pin "P$9") (pinfunction "PIO1_8/CT16B1_CAP0_P$9") (pintype "bidirectional"))
    )
    (net (code "55") (name "unconnected-(U1-PIO1_9{slash}CT16B1_MAT0-PadP$17)") (class "Default")
      (node (ref "U1") (pin "P$17") (pinfunction "PIO1_9/CT16B1_MAT0_P$17") (pintype "bidirectional"))
    )
    (net (code "56") (name "unconnected-(U1-PIO1_10{slash}AD6{slash}CT16B1_MAT1-PadP$30)") (class "Default")
      (node (ref "U1") (pin "P$30") (pinfunction "PIO1_10/AD6/CT16B1_MAT1_P$30") (pintype "bidirectional"))
    )
    (net (code "57") (name "unconnected-(U1-PIO1_11{slash}AD7-PadP$42)") (class "Default")
      (node (ref "U1") (pin "P$42") (pinfunction "PIO1_11/AD7_P$42") (pintype "bidirectional"))
    )
    (net (code "58") (name "unconnected-(U1-PIO2_2{slash}~{DCD}{slash}MISO1-PadP$26)") (class "Default")
      (node (ref "U1") (pin "P$26") (pinfunction "PIO2_2/~{DCD}/MISO1_P$26") (pintype "bidirectional"))
    )
    (net (code "59") (name "unconnected-(U1-PIO2_3{slash}~{RI}{slash}MOSI1-PadP$38)") (class "Default")
      (node (ref "U1") (pin "P$38") (pinfunction "PIO2_3/~{RI}/MOSI1_P$38") (pintype "bidirectional"))
    )
    (net (code "60") (name "unconnected-(U1-PIO2_4-PadP$18)") (class "Default")
      (node (ref "U1") (pin "P$18") (pinfunction "PIO2_4_P$18") (pintype "bidirectional"))
    )
    (net (code "61") (name "unconnected-(U1-PIO2_5-PadP$21)") (class "Default")
      (node (ref "U1") (pin "P$21") (pinfunction "PIO2_5_P$21") (pintype "bidirectional"))
    )
    (net (code "62") (name "unconnected-(U1-PIO2_6-PadP$1)") (class "Default")
      (node (ref "U1") (pin "P$1") (pinfunction "PIO2_6_P$1") (pintype "bidirectional"))
    )
    (net (code "63") (name "unconnected-(U1-PIO2_9-PadP$24)") (class "Default")
      (node (ref "U1") (pin "P$24") (pinfunction "PIO2_9_P$24") (pintype "bidirectional"))
    )
    (net (code "64") (name "unconnected-(U1-PIO2_11{slash}SCK0-PadP$31)") (class "Default")
      (node (ref "U1") (pin "P$31") (pinfunction "PIO2_11/SCK0_P$31") (pintype "bidirectional"))
    )
    (net (code "65") (name "unconnected-(U1-PIO3_1{slash}~{DSR}-PadP$37)") (class "Default")
      (node (ref "U1") (pin "P$37") (pinfunction "PIO3_1/~{DSR}_P$37") (pintype "bidirectional"))
    )
    (net (code "66") (name "unconnected-(U1-PIO3_2{slash}~{DCD}-PadP$43)") (class "Default")
      (node (ref "U1") (pin "P$43") (pinfunction "PIO3_2/~{DCD}_P$43") (pintype "bidirectional"))
    )
    (net (code "67") (name "unconnected-(U1-R{slash}PIO1_2{slash}AD3{slash}CT32B1_MAT1-PadP$35)") (class "Default")
      (node (ref "U1") (pin "P$35") (pinfunction "R/PIO1_2/AD3/CT32B1_MAT1_P$35") (pintype "bidirectional"))
    )
    (net (code "68") (name "unconnected-(U1-SWCLK{slash}PIO0_10{slash}SCK0{slash}CT16B0_MAT2-PadP$29)") (class "Default")
      (node (ref "U1") (pin "P$29") (pinfunction "SWCLK/PIO0_10/SCK0/CT16B0_MAT2_P$29") (pintype "bidirectional"))
    )
    (net (code "69") (name "unconnected-(U1-SWDIO{slash}PIO1_3{slash}AD4{slash}CT32B1_MAT2-PadP$39)") (class "Default")
      (node (ref "U1") (pin "P$39") (pinfunction "SWDIO/PIO1_3/AD4/CT32B1_MAT2_P$39") (pintype "bidirectional"))
    )
    (net (code "70") (name "unconnected-(U2-VREF-PadP$5)") (class "Default")
      (node (ref "U2") (pin "P$5") (pinfunction "VREF_P$5") (pintype "bidirectional"))
    )
    (net (code "71") (name "unconnected-(VR1-ON{slash}OFF-PadP$5)") (class "Default")
      (node (ref "VR1") (pin "P$5") (pinfunction "ON/OFF_P$5") (pintype "bidirectional"))
    )
    (net (code "72") (name "unconnected-(VR1-SS-PadP$2)") (class "Default")
      (node (ref "VR1") (pin "P$2") (pinfunction "SS_P$2") (pintype "bidirectional"))
    )
    (net (code "73") (name "unconnected-(VR1-SYNC-PadP$3)") (class "Default")
      (node (ref "VR1") (pin "P$3") (pinfunction "SYNC_P$3") (pintype "bidirectional"))
    )
  )
)
